# Power.net
KiCad netlist of a schematic drawn in Altium Designer
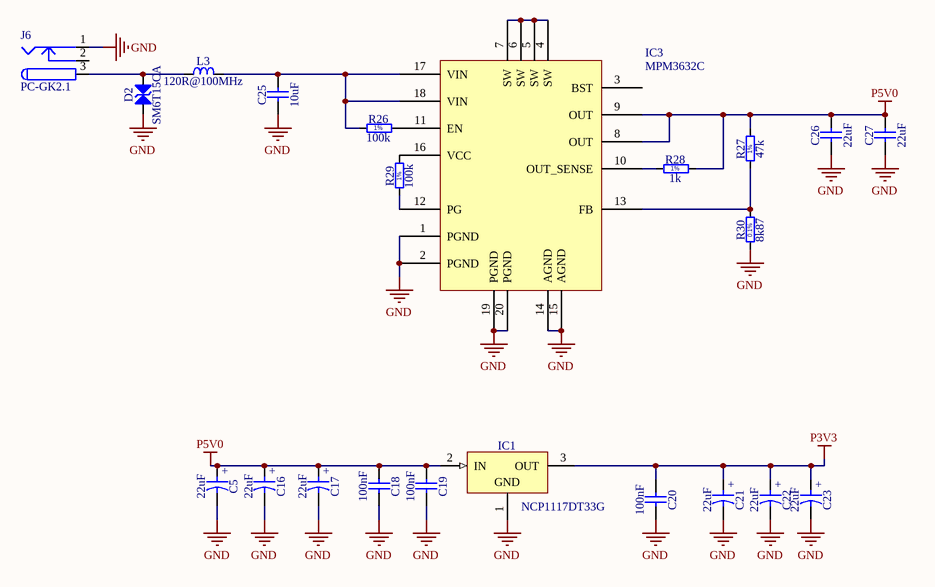
[diagram p0: Power.SchDoc]

(export (version "E")
  (design (tool "Eeschema 10.0.6"))
  (components
    (comp (ref "C5")
      (value "22uF")
      (footprint "CAPAE430X540N")
      (description "Polarised capacitor")
      (fields
        (field (name "PART NUMBER") "CAE430-540_22UF_10V_20%")
        (field (name "VOLTAGE") "10V")
        (field (name "AUTHOR") "CERN DEM JLC")
      )
      (libsource (lib "Capacitors") (part "Capacitor - polarized"))
    )
    (comp (ref "C16")
      (value "22uF")
      (footprint "CAPAE430X540N")
      (description "Polarised capacitor")
      (fields
        (field (name "PART NUMBER") "CAE430-540_22UF_10V_20%")
        (field (name "VOLTAGE") "10V")
        (field (name "AUTHOR") "CERN DEM JLC")
      )
      (libsource (lib "Capacitors") (part "Capacitor - polarized"))
    )
    (comp (ref "C17")
      (value "22uF")
      (footprint "CAPAE430X540N")
      (description "Polarised capacitor")
      (fields
        (field (name "PART NUMBER") "CAE430-540_22UF_10V_20%")
        (field (name "VOLTAGE") "10V")
        (field (name "AUTHOR") "CERN DEM JLC")
      )
      (libsource (lib "Capacitors") (part "Capacitor - polarized"))
    )
    (comp (ref "C18")
      (value "100nF")
      (footprint "CAPC1608X87N")
      (description "Non-polarised capacitor")
      (fields
        (field (name "PART NUMBER") "CC0603_100NF_50V_10%_X5R")
        (field (name "VOLTAGE") "50V")
        (field (name "AUTHOR") "CERN DEM MR")
      )
      (libsource (lib "Capacitors") (part "Capacitor - non polarized"))
    )
    (comp (ref "C19")
      (value "100nF")
      (footprint "CAPC1608X87N")
      (description "Non-polarised capacitor")
      (fields
        (field (name "PART NUMBER") "CC0603_100NF_50V_10%_X5R")
        (field (name "VOLTAGE") "50V")
        (field (name "AUTHOR") "CERN DEM MR")
      )
      (libsource (lib "Capacitors") (part "Capacitor - non polarized"))
    )
    (comp (ref "C20")
      (value "100nF")
      (footprint "CAPC1608X87N")
      (description "Non-polarised capacitor")
      (fields
        (field (name "PART NUMBER") "CC0603_100NF_50V_10%_X5R")
        (field (name "VOLTAGE") "50V")
        (field (name "AUTHOR") "CERN DEM MR")
      )
      (libsource (lib "Capacitors") (part "Capacitor - non polarized"))
    )
    (comp (ref "C21")
      (value "22uF")
      (footprint "CAPAE430X540N")
      (description "Polarised capacitor")
      (fields
        (field (name "PART NUMBER") "CAE430-540_22UF_10V_20%")
        (field (name "VOLTAGE") "10V")
        (field (name "AUTHOR") "CERN DEM JLC")
      )
      (libsource (lib "Capacitors") (part "Capacitor - polarized"))
    )
    (comp (ref "C22")
      (value "22uF")
      (footprint "CAPAE430X540N")
      (description "Polarised capacitor")
      (fields
        (field (name "PART NUMBER") "CAE430-540_22UF_10V_20%")
        (field (name "VOLTAGE") "10V")
        (field (name "AUTHOR") "CERN DEM JLC")
      )
      (libsource (lib "Capacitors") (part "Capacitor - polarized"))
    )
    (comp (ref "C23")
      (value "22uF")
      (footprint "CAPAE430X540N")
      (description "Polarised capacitor")
      (fields
        (field (name "PART NUMBER") "CAE430-540_22UF_10V_20%")
        (field (name "VOLTAGE") "10V")
        (field (name "AUTHOR") "CERN DEM JLC")
      )
      (libsource (lib "Capacitors") (part "Capacitor - polarized"))
    )
    (comp (ref "C25")
      (value "10uF")
      (footprint "CAPC2012X135N")
      (description "Non-polarised capacitor")
      (fields
        (field (name "PART NUMBER") "CC0805_10UF_16V_10%_X5R")
        (field (name "VOLTAGE") "16V")
        (field (name "AUTHOR") "CERN DEM JLC")
      )
      (libsource (lib "Capacitors") (part "Capacitor - non polarized"))
    )
    (comp (ref "C26")
      (value "22uF")
      (footprint "CAPC2012X135N")
      (description "Non-polarised capacitor")
      (fields
        (field (name "PART NUMBER") "CC0805_22UF_16V_10%_X5R")
        (field (name "VOLTAGE") "16V")
        (field (name "AUTHOR") "CERN DEM JLC")
      )
      (libsource (lib "Capacitors") (part "Capacitor - non polarized"))
    )
    (comp (ref "C27")
      (value "22uF")
      (footprint "CAPC2012X135N")
      (description "Non-polarised capacitor")
      (fields
        (field (name "PART NUMBER") "CC0805_22UF_16V_10%_X5R")
        (field (name "VOLTAGE") "16V")
        (field (name "AUTHOR") "CERN DEM JLC")
      )
      (libsource (lib "Capacitors") (part "Capacitor - non polarized"))
    )
    (comp (ref "D2")
      (value "SM6T15CA")
      (footprint "DIOM5436X265N")
      (description "Transient Voltage Suppressor Diode (Bi-Directional)")
      (fields
        (field (name "VOLTAGE") "15V")
        (field (name "POWER") "600W")
        (field (name "AUTHOR") "CERN DEM JLC")
      )
      (libsource (lib "ICs And Semiconductors") (part "Diode TVS Bi-Directional"))
    )
    (comp (ref "IC1")
      (value "NCP1117DT33G")
      (footprint "TO228P991X239-3N-R552X520")
      (description "3-Terminal Regulator 1=GND 2=IN 3=OUT")
      (fields (field (name "MANUFACTURER") "ON SEMICONDUCTOR") (field (name "AUTHOR") "CERN DEM JLC"))
      (libsource (lib "ICs And Semiconductors") (part "REG3 1GND-2IN-3OUT"))
    )
    (comp (ref "IC3")
      (value "MPM3632C")
      (footprint "PCBComponent_1 - duplicate")
      (libsource (lib "MG_lib") (part "MPM3632C"))
    )
    (comp (ref "J6")
      (value "PC-GK2.1")
      (footprint "DC2020")
      (description "Low Voltage Power Supply Connector (maritex)")
      (fields (field (name "PUBLISHER") "Altium Limited"))
      (libsource (lib "LIBRARY_SCH") (part "CON_DC_JACK_TH"))
    )
    (comp (ref "L3")
      (value "120R@100MHz")
      (footprint "INDC1608X65N")
      (description "Inductor")
      (fields
        (field (name "PART NUMBER") "IND0603_MURATA_BLM18SG121TN1D")
        (field (name "POWER") "3A")
        (field (name "AUTHOR") "CERN DEM JLC")
      )
      (libsource (lib "Inductors & Transformers") (part "Inductor"))
    )
    (comp (ref "R26")
      (value "100k")
      (footprint "RESC1005X40N")
      (description "Resistor - 1%")
      (fields
        (field (name "PART NUMBER") "R0402_100K_1%_0.0625W_100PPM")
        (field (name "POWER") "0.0625W")
        (field (name "AUTHOR") "CERN DEM JLC")
      )
      (libsource (lib "Resistors") (part "Resistor - 1%"))
    )
    (comp (ref "R27")
      (value "47k")
      (footprint "RESC1005X40N")
      (description "Resistor - 1%")
      (fields
        (field (name "PART NUMBER") "R0402_47K_1%_0.0625W_100PPM")
        (field (name "POWER") "0.0625W")
        (field (name "AUTHOR") "CERN DEM JLC")
      )
      (libsource (lib "Resistors") (part "Resistor - 1%"))
    )
    (comp (ref "R28")
      (value "1k")
      (footprint "RESC1608X50N")
      (description "Resistor - 1%")
      (fields
        (field (name "PART NUMBER") "R0805_1K_1%_0.33W_100PPM_VISHAY_CRCW-HP")
        (field (name "POWER") "0.33W")
        (field (name "AUTHOR") "CERN DEM JLC")
      )
      (libsource (lib "Resistors") (part "Resistor - 1%"))
    )
    (comp (ref "R29")
      (value "100k")
      (footprint "RESC1005X40N")
      (description "Resistor - 1%")
      (fields
        (field (name "PART NUMBER") "R0402_100K_1%_0.0625W_100PPM")
        (field (name "POWER") "0.0625W")
        (field (name "AUTHOR") "CERN DEM JLC")
      )
      (libsource (lib "Resistors") (part "Resistor - 1%"))
    )
    (comp (ref "R30")
      (value "8k87")
      (footprint "RESC1608X55N")
      (description "Resistor - 0.1%")
      (fields
        (field (name "PART NUMBER") "R0603_8K87_0.1%_0.063W_10PPM")
        (field (name "POWER") "0.063W")
        (field (name "AUTHOR") "CERN DEM JLC")
      )
      (libsource (lib "Resistors") (part "Resistor - 0.1%"))
    )
  )
  (nets
    (net (code "1") (name "GND") (class "Default")
      (node (ref "C16") (pin "2") (pinfunction "2_2") (pintype "passive"))
      (node (ref "C17") (pin "2") (pinfunction "2_2") (pintype "passive"))
      (node (ref "C18") (pin "2") (pinfunction "2_2") (pintype "passive"))
      (node (ref "C19") (pin "2") (pinfunction "2_2") (pintype "passive"))
      (node (ref "C20") (pin "2") (pinfunction "2_2") (pintype "passive"))
      (node (ref "C21") (pin "2") (pinfunction "2_2") (pintype "passive"))
      (node (ref "C22") (pin "2") (pinfunction "2_2") (pintype "passive"))
      (node (ref "C23") (pin "2") (pinfunction "2_2") (pintype "passive"))
      (node (ref "C25") (pin "1") (pinfunction "1_1") (pintype "passive"))
      (node (ref "C26") (pin "1") (pinfunction "1_1") (pintype "passive"))
      (node (ref "C27") (pin "1") (pinfunction "1_1") (pintype "passive"))
      (node (ref "C5") (pin "2") (pinfunction "2_2") (pintype "passive"))
      (node (ref "D2") (pin "2") (pinfunction "A_2") (pintype "passive"))
      (node (ref "IC1") (pin "1") (pinfunction "GND_1") (pintype "power_in"))
      (node (ref "IC3") (pin "1") (pinfunction "PGND_1") (pintype "power_in"))
      (node (ref "IC3") (pin "14") (pinfunction "AGND_14") (pintype "power_in"))
      (node (ref "IC3") (pin "15") (pinfunction "AGND_15") (pintype "power_in"))
      (node (ref "IC3") (pin "19") (pinfunction "PGND_19") (pintype "power_in"))
      (node (ref "IC3") (pin "2") (pinfunction "PGND_2") (pintype "power_in"))
      (node (ref "IC3") (pin "20") (pinfunction "PGND_20") (pintype "power_in"))
      (node (ref "J6") (pin "1") (pintype "power_in"))
      (node (ref "R30") (pin "1") (pinfunction "1_1") (pintype "passive"))
    )
    (net (code "2") (name "Net-(C25-Pad2)") (class "Default")
      (node (ref "C25") (pin "2") (pinfunction "2_2") (pintype "passive"))
      (node (ref "IC3") (pin "17") (pinfunction "VIN_17") (pintype "power_in"))
      (node (ref "IC3") (pin "18") (pinfunction "VIN_18") (pintype "power_in"))
      (node (ref "L3") (pin "2") (pinfunction "2_2") (pintype "passive"))
      (node (ref "R26") (pin "1") (pinfunction "1_1") (pintype "passive"))
    )
    (net (code "3") (name "Net-(D2-C)") (class "Default")
      (node (ref "D2") (pin "1") (pinfunction "C_1") (pintype "passive"))
      (node (ref "J6") (pin "3") (pintype "power_in"))
      (node (ref "L3") (pin "1") (pinfunction "1_1") (pintype "passive"))
    )
    (net (code "4") (name "Net-(IC3-EN)") (class "Default")
      (node (ref "IC3") (pin "11") (pinfunction "EN_11") (pintype "power_in"))
      (node (ref "R26") (pin "2") (pinfunction "2_2") (pintype "passive"))
    )
    (net (code "5") (name "Net-(IC3-FB)") (class "Default")
      (node (ref "IC3") (pin "13") (pinfunction "FB_13") (pintype "power_in"))
      (node (ref "R27") (pin "1") (pinfunction "1_1") (pintype "passive"))
      (node (ref "R30") (pin "2") (pinfunction "2_2") (pintype "passive"))
    )
    (net (code "6") (name "Net-(IC3-OUT_SENSE)") (class "Default")
      (node (ref "IC3") (pin "10") (pinfunction "OUT_SENSE_10") (pintype "power_in"))
      (node (ref "R28") (pin "1") (pinfunction "1_1") (pintype "passive"))
    )
    (net (code "7") (name "Net-(IC3-PG)") (class "Default")
      (node (ref "IC3") (pin "12") (pinfunction "PG_12") (pintype "power_in"))
      (node (ref "R29") (pin "1") (pinfunction "1_1") (pintype "passive"))
    )
    (net (code "8") (name "Net-(IC3-SW-Pad4)") (class "Default")
      (node (ref "IC3") (pin "4") (pinfunction "SW_4") (pintype "power_in"))
      (node (ref "IC3") (pin "5") (pinfunction "SW_5") (pintype "power_in"))
      (node (ref "IC3") (pin "6") (pinfunction "SW_6") (pintype "power_in"))
      (node (ref "IC3") (pin "7") (pinfunction "SW_7") (pintype "power_in"))
    )
    (net (code "9") (name "Net-(IC3-VCC)") (class "Default")
      (node (ref "IC3") (pin "16") (pinfunction "VCC_16") (pintype "power_in"))
      (node (ref "R29") (pin "2") (pinfunction "2_2") (pintype "passive"))
    )
    (net (code "10") (name "P3V3") (class "Default")
      (node (ref "C20") (pin "1") (pinfunction "1_1") (pintype "passive"))
      (node (ref "C21") (pin "1") (pinfunction "1_1") (pintype "passive"))
      (node (ref "C22") (pin "1") (pinfunction "1_1") (pintype "passive"))
      (node (ref "C23") (pin "1") (pinfunction "1_1") (pintype "passive"))
      (node (ref "IC1") (pin "3") (pinfunction "OUT_3") (pintype "power_in"))
    )
    (net (code "11") (name "P5V0") (class "Default")
      (node (ref "C16") (pin "1") (pinfunction "1_1") (pintype "passive"))
      (node (ref "C17") (pin "1") (pinfunction "1_1") (pintype "passive"))
      (node (ref "C18") (pin "1") (pinfunction "1_1") (pintype "passive"))
      (node (ref "C19") (pin "1") (pinfunction "1_1") (pintype "passive"))
      (node (ref "C26") (pin "2") (pinfunction "2_2") (pintype "passive"))
      (node (ref "C27") (pin "2") (pinfunction "2_2") (pintype "passive"))
      (node (ref "C5") (pin "1") (pinfunction "1_1") (pintype "passive"))
      (node (ref "IC1") (pin "2") (pinfunction "IN_2") (pintype "input"))
      (node (ref "IC3") (pin "8") (pinfunction "OUT_8") (pintype "power_in"))
      (node (ref "IC3") (pin "9") (pinfunction "OUT_9") (pintype "power_in"))
      (node (ref "R27") (pin "2") (pinfunction "2_2") (pintype "passive"))
      (node (ref "R28") (pin "2") (pinfunction "2_2") (pintype "passive"))
    )
    (net (code "12") (name "unconnected-(IC3-BST-Pad3)") (class "Default")
      (node (ref "IC3") (pin "3") (pinfunction "BST_3") (pintype "power_in"))
    )
    (net (code "13") (name "unconnected-(J6-Pad2)") (class "Default")
      (node (ref "J6") (pin "2") (pintype "power_in"))
    )
  )
)
